# Control_Board.net
KiCad netlist of a schematic drawn in EAGLE
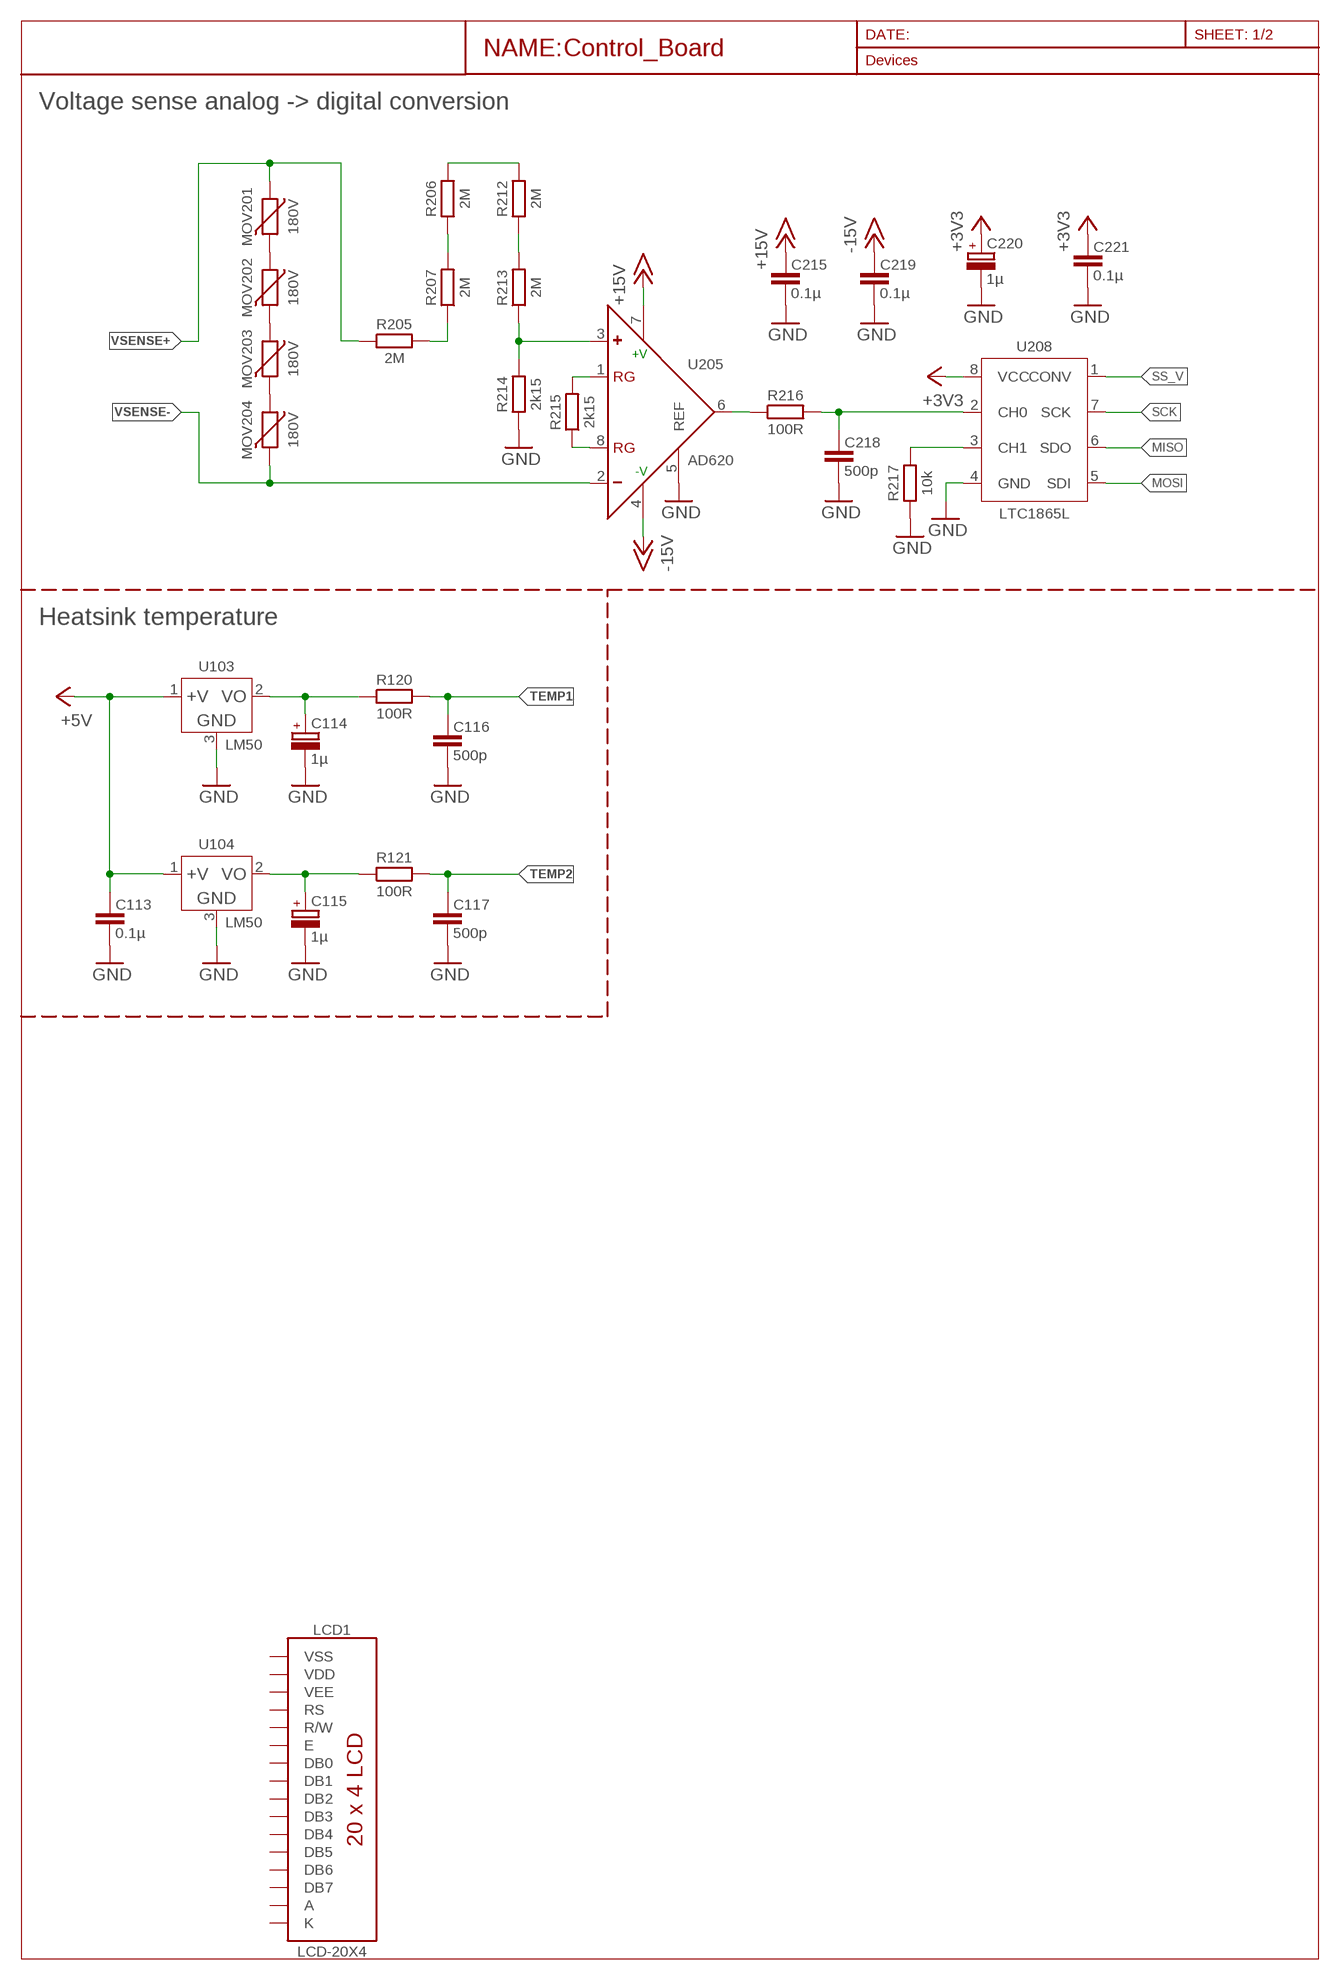
[diagram p0: schematic, sheet 1]
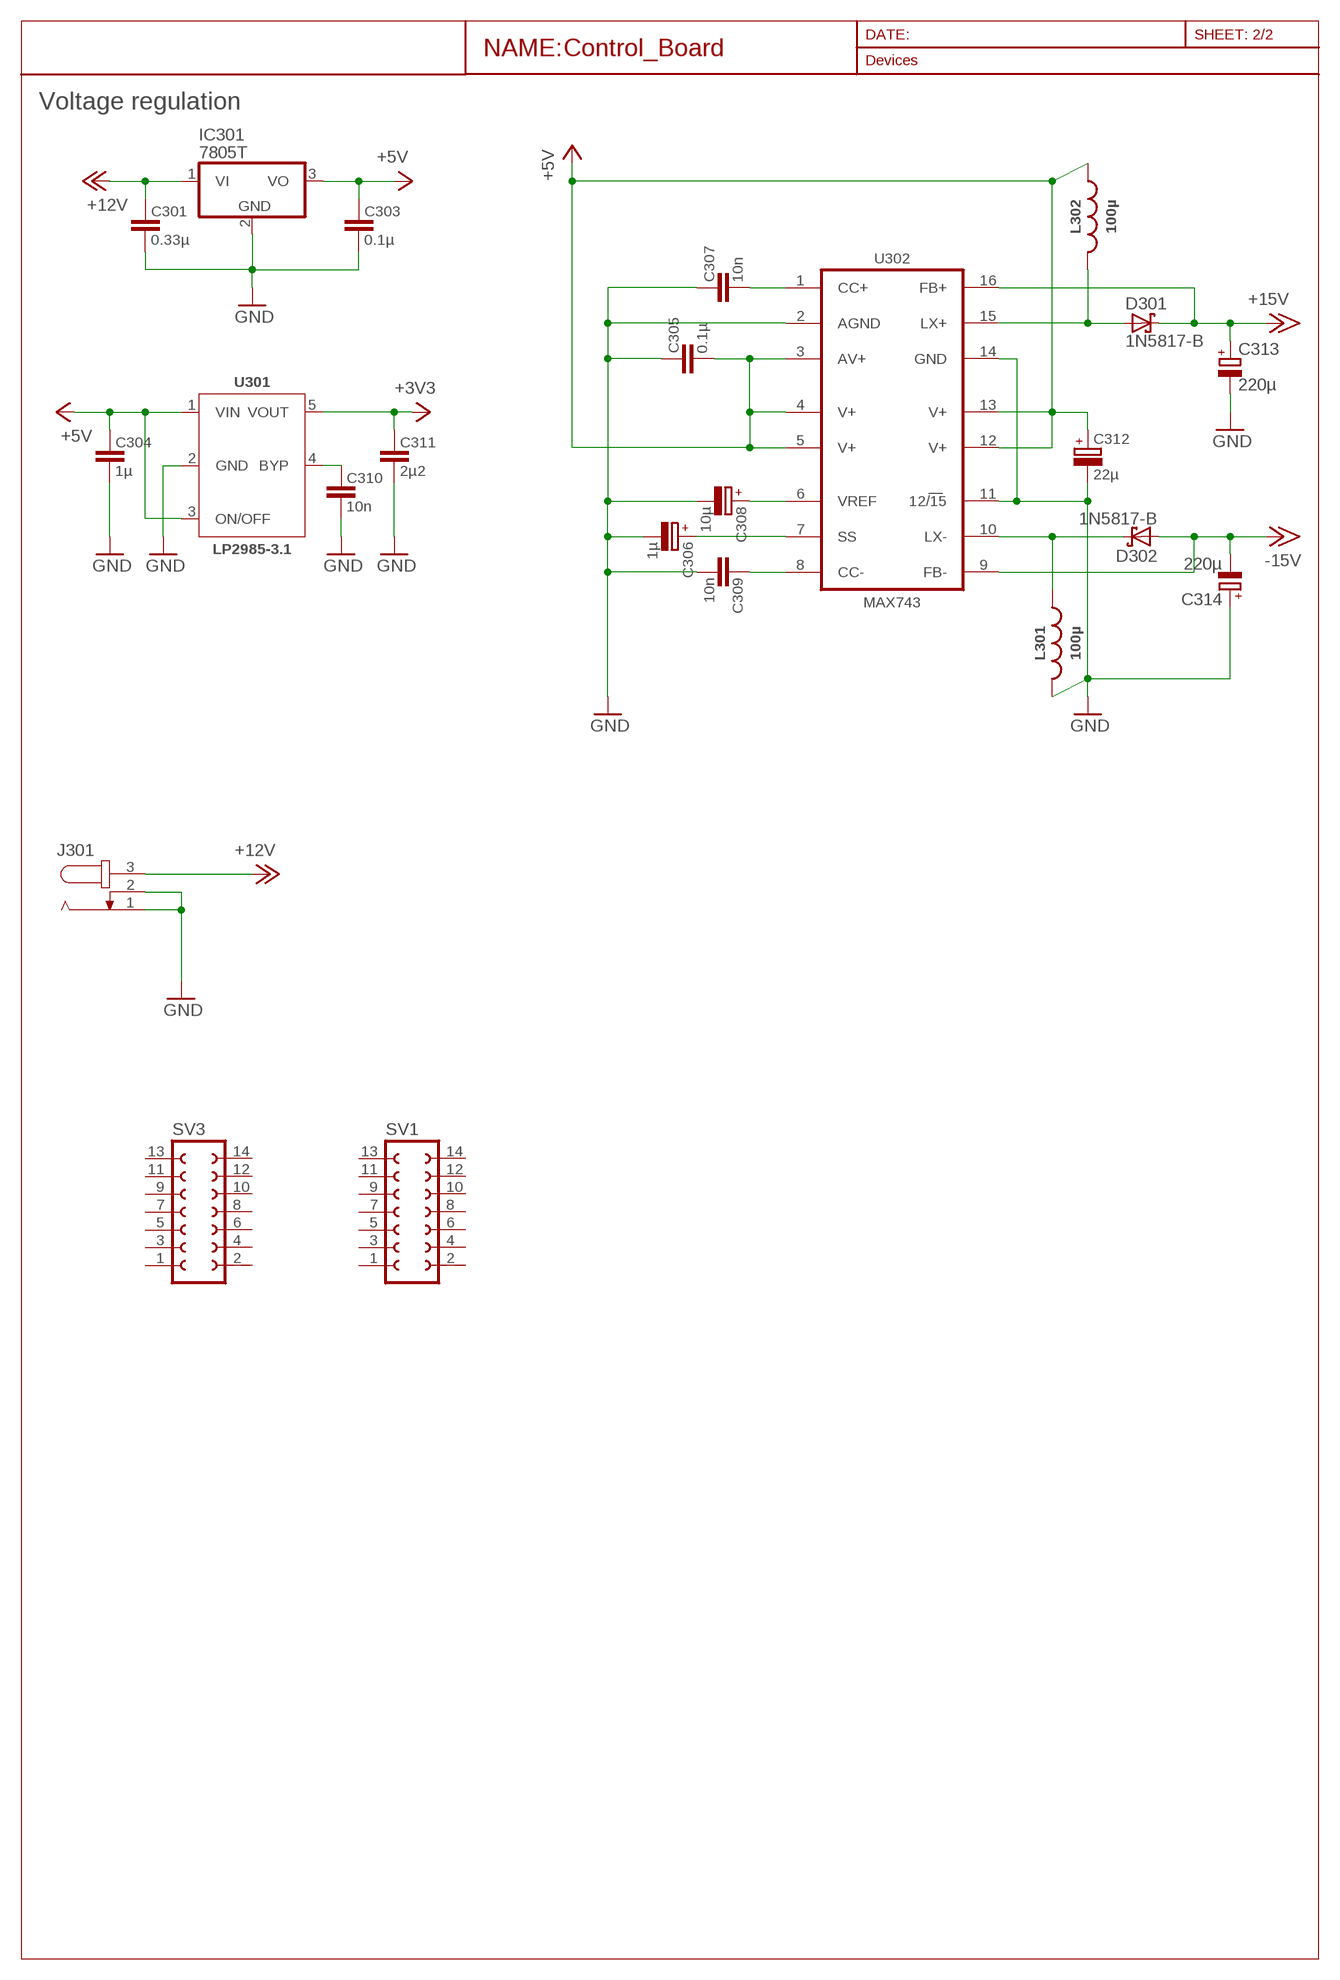
[diagram p1: schematic, sheet 2]

(export (version "E")
  (design (tool "Eeschema 10.0.6"))
  (components
    (comp (ref "C113")
      (value "0.1µ")
      (footprint "eagle-import:C3216")
      (libsource (lib "eagle-import") (part "C-EU-3216"))
    )
    (comp (ref "C114")
      (value "1µ")
      (footprint "eagle-import:CT3216")
      (libsource (lib "eagle-import") (part "CPOL-3216-A"))
    )
    (comp (ref "C115")
      (value "1µ")
      (footprint "eagle-import:CT3216")
      (libsource (lib "eagle-import") (part "CPOL-3216-A"))
    )
    (comp (ref "C116")
      (value "500p")
      (footprint "eagle-import:C1608")
      (libsource (lib "eagle-import") (part "C-EU-1608"))
    )
    (comp (ref "C117")
      (value "500p")
      (footprint "eagle-import:C1608")
      (libsource (lib "eagle-import") (part "C-EU-1608"))
    )
    (comp (ref "C215")
      (value "0.1µ")
      (footprint "eagle-import:C3216")
      (libsource (lib "eagle-import") (part "C-EU-3216"))
    )
    (comp (ref "C218")
      (value "500p")
      (footprint "eagle-import:C1608")
      (libsource (lib "eagle-import") (part "C-EU-1608"))
    )
    (comp (ref "C219")
      (value "0.1µ")
      (footprint "eagle-import:C3216")
      (libsource (lib "eagle-import") (part "C-EU-3216"))
    )
    (comp (ref "C220")
      (value "1µ")
      (footprint "eagle-import:CT3216")
      (libsource (lib "eagle-import") (part "CPOL-3216-A"))
    )
    (comp (ref "C221")
      (value "0.1µ")
      (footprint "eagle-import:C3216")
      (libsource (lib "eagle-import") (part "C-EU-3216"))
    )
    (comp (ref "LCD1")
      (value "LCD-20X4")
      (footprint "eagle-import:4X20_LED")
      (libsource (lib "eagle-import") (part "LCD-20X4"))
    )
    (comp (ref "MOV201")
      (value "180V")
      (footprint "eagle-import:R3225W")
      (libsource (lib "eagle-import") (part "MOV-3225"))
    )
    (comp (ref "MOV202")
      (value "180V")
      (footprint "eagle-import:R3225W")
      (libsource (lib "eagle-import") (part "MOV-3225"))
    )
    (comp (ref "MOV203")
      (value "180V")
      (footprint "eagle-import:R3225W")
      (libsource (lib "eagle-import") (part "MOV-3225"))
    )
    (comp (ref "MOV204")
      (value "180V")
      (footprint "eagle-import:R3225W")
      (libsource (lib "eagle-import") (part "MOV-3225"))
    )
    (comp (ref "R120")
      (value "100R")
      (footprint "eagle-import:R2012W")
      (libsource (lib "eagle-import") (part "R-EU-2012"))
    )
    (comp (ref "R121")
      (value "100R")
      (footprint "eagle-import:R2012W")
      (libsource (lib "eagle-import") (part "R-EU-2012"))
    )
    (comp (ref "R205")
      (value "2M")
      (footprint "eagle-import:R3216W")
      (libsource (lib "eagle-import") (part "R-EU-3216"))
    )
    (comp (ref "R206")
      (value "2M")
      (footprint "eagle-import:R3216W")
      (libsource (lib "eagle-import") (part "R-EU-3216"))
    )
    (comp (ref "R207")
      (value "2M")
      (footprint "eagle-import:R3216W")
      (libsource (lib "eagle-import") (part "R-EU-3216"))
    )
    (comp (ref "R212")
      (value "2M")
      (footprint "eagle-import:R3216W")
      (libsource (lib "eagle-import") (part "R-EU-3216"))
    )
    (comp (ref "R213")
      (value "2M")
      (footprint "eagle-import:R3216W")
      (libsource (lib "eagle-import") (part "R-EU-3216"))
    )
    (comp (ref "R214")
      (value "2k15")
      (footprint "eagle-import:R2012W")
      (libsource (lib "eagle-import") (part "R-EU-2012"))
    )
    (comp (ref "R215")
      (value "2k15")
      (footprint "eagle-import:R2012W")
      (libsource (lib "eagle-import") (part "R-EU-2012"))
    )
    (comp (ref "R216")
      (value "100R")
      (footprint "eagle-import:R2012W")
      (libsource (lib "eagle-import") (part "R-EU-2012"))
    )
    (comp (ref "R217")
      (value "10k")
      (footprint "eagle-import:R1608")
      (libsource (lib "eagle-import") (part "R-EU-1608"))
    )
    (comp (ref "U103")
      (value "LM50")
      (footprint "eagle-import:SOT23W")
      (libsource (lib "eagle-import") (part "LM50"))
    )
    (comp (ref "U104")
      (value "LM50")
      (footprint "eagle-import:SOT23W")
      (libsource (lib "eagle-import") (part "LM50"))
    )
    (comp (ref "U205")
      (value "AD620")
      (footprint "eagle-import:SO8")
      (libsource (lib "eagle-import") (part "AD620R-8"))
    )
    (comp (ref "U208")
      (value "LTC1865L")
      (footprint "eagle-import:SO8")
      (libsource (lib "eagle-import") (part "LTC1865L"))
    )
    (comp (ref "C301")
      (value "0.33µ")
      (footprint "eagle-import:C3216")
      (libsource (lib "eagle-import") (part "C-EU-3216"))
    )
    (comp (ref "C303")
      (value "0.1µ")
      (footprint "eagle-import:C3216")
      (libsource (lib "eagle-import") (part "C-EU-3216"))
    )
    (comp (ref "C304")
      (value "1µ")
      (footprint "eagle-import:C3216")
      (libsource (lib "eagle-import") (part "C-EU-3216"))
    )
    (comp (ref "C305")
      (value "0.1µ")
      (footprint "eagle-import:C3216")
      (libsource (lib "eagle-import") (part "C-EU-3216"))
    )
    (comp (ref "C306")
      (value "1µ")
      (footprint "eagle-import:CT3216")
      (libsource (lib "eagle-import") (part "CPOL-3216-A"))
    )
    (comp (ref "C307")
      (value "10n")
      (footprint "eagle-import:C3216")
      (libsource (lib "eagle-import") (part "C-EU-3216"))
    )
    (comp (ref "C308")
      (value "10µ")
      (footprint "eagle-import:CT6032")
      (libsource (lib "eagle-import") (part "CPOL-6032-C"))
    )
    (comp (ref "C309")
      (value "10n")
      (footprint "eagle-import:C3216")
      (libsource (lib "eagle-import") (part "C-EU-3216"))
    )
    (comp (ref "C310")
      (value "10n")
      (footprint "eagle-import:C3216")
      (libsource (lib "eagle-import") (part "C-EU-3216"))
    )
    (comp (ref "C311")
      (value "2µ2")
      (footprint "eagle-import:C3216")
      (libsource (lib "eagle-import") (part "C-EU-3216"))
    )
    (comp (ref "C312")
      (value "22µ")
      (footprint "eagle-import:CT6032")
      (libsource (lib "eagle-import") (part "CPOL-6032-C"))
    )
    (comp (ref "C313")
      (value "220µ")
      (footprint "eagle-import:E3,5-10")
      (libsource (lib "eagle-import") (part "CPOL-EUE3.5-10"))
    )
    (comp (ref "C314")
      (value "220µ")
      (footprint "eagle-import:E3,5-10")
      (libsource (lib "eagle-import") (part "CPOL-EUE3.5-10"))
    )
    (comp (ref "D301")
      (value "1N5817-B")
      (footprint "eagle-import:DO41-7.6")
      (libsource (lib "eagle-import") (part "1N5817-B"))
    )
    (comp (ref "D302")
      (value "1N5817-B")
      (footprint "eagle-import:DO41-7.6")
      (libsource (lib "eagle-import") (part "1N5817-B"))
    )
    (comp (ref "IC301")
      (value "7805T")
      (footprint "eagle-import:TO220H")
      (libsource (lib "eagle-import") (part "78T05"))
    )
    (comp (ref "J301")
      (value "JACK-PLUG0")
      (footprint "eagle-import:SPC4077")
      (libsource (lib "eagle-import") (part "JACK-PLUG0"))
    )
    (comp (ref "L301")
      (value "100µ")
      (footprint "eagle-import:SRN1060")
      (libsource (lib "eagle-import") (part "L-EUSRN1060"))
    )
    (comp (ref "L302")
      (value "100µ")
      (footprint "eagle-import:SRN1060")
      (libsource (lib "eagle-import") (part "L-EUSRN1060"))
    )
    (comp (ref "SV1")
      (value "FE07-2W")
      (footprint "eagle-import:FE07-2W")
      (libsource (lib "eagle-import") (part "FE07-2W"))
    )
    (comp (ref "SV3")
      (value "FE07-2W")
      (footprint "eagle-import:FE07-2W")
      (libsource (lib "eagle-import") (part "FE07-2W"))
    )
    (comp (ref "U301")
      (value "LP2985-3.1")
      (footprint "eagle-import:SOT23-5L")
      (libsource (lib "eagle-import") (part "LP2985-3.1"))
    )
    (comp (ref "U302")
      (value "MAX743")
      (footprint "eagle-import:SO16W")
      (libsource (lib "eagle-import") (part "MAX743WE"))
    )
  )
  (nets
    (net (code "1") (name "+3V3") (class "Default")
      (node (ref "C220") (pin "+") (pinfunction "+_+") (pintype "passive"))
      (node (ref "C221") (pin "1") (pinfunction "1_1") (pintype "passive"))
      (node (ref "C311") (pin "1") (pinfunction "1_1") (pintype "passive"))
      (node (ref "U208") (pin "8") (pinfunction "VCC_8") (pintype "power_in"))
      (node (ref "U301") (pin "5") (pinfunction "VOUT_5") (pintype "power_in"))
    )
    (net (code "2") (name "+5V") (class "Default")
      (node (ref "C113") (pin "1") (pinfunction "1_1") (pintype "passive"))
      (node (ref "C303") (pin "1") (pinfunction "1_1") (pintype "passive"))
      (node (ref "C304") (pin "1") (pinfunction "1_1") (pintype "passive"))
      (node (ref "C305") (pin "2") (pinfunction "2_2") (pintype "passive"))
      (node (ref "C312") (pin "+") (pinfunction "+_+") (pintype "passive"))
      (node (ref "IC301") (pin "3") (pinfunction "VO_3") (pintype "passive"))
      (node (ref "L302") (pin "1") (pinfunction "1_1") (pintype "passive"))
      (node (ref "U103") (pin "1") (pinfunction "+V_1") (pintype "power_in"))
      (node (ref "U104") (pin "1") (pinfunction "+V_1") (pintype "power_in"))
      (node (ref "U301") (pin "1") (pinfunction "VIN_1") (pintype "power_in"))
      (node (ref "U301") (pin "3") (pinfunction "ON/OFF_3") (pintype "input"))
      (node (ref "U302") (pin "12") (pinfunction "V+_12") (pintype "input"))
      (node (ref "U302") (pin "13") (pinfunction "V+_13") (pintype "input"))
      (node (ref "U302") (pin "3") (pinfunction "AV+_3") (pintype "input"))
      (node (ref "U302") (pin "4") (pinfunction "V+_4") (pintype "input"))
      (node (ref "U302") (pin "5") (pinfunction "V+_5") (pintype "input"))
    )
    (net (code "3") (name "+12V") (class "Default")
      (node (ref "C301") (pin "1") (pinfunction "1_1") (pintype "passive"))
      (node (ref "IC301") (pin "1") (pinfunction "VI_1") (pintype "input"))
      (node (ref "J301") (pin "3") (pinfunction "3_3") (pintype "passive"))
    )
    (net (code "4") (name "+15V") (class "Default")
      (node (ref "C215") (pin "1") (pinfunction "1_1") (pintype "passive"))
      (node (ref "C313") (pin "+") (pinfunction "+_+") (pintype "passive"))
      (node (ref "D301") (pin "C") (pinfunction "C_C") (pintype "passive"))
      (node (ref "U205") (pin "7") (pinfunction "+V_7") (pintype "power_in"))
      (node (ref "U302") (pin "16") (pinfunction "FB+_16") (pintype "input"))
    )
    (net (code "5") (name "-15V") (class "Default")
      (node (ref "C219") (pin "1") (pinfunction "1_1") (pintype "passive"))
      (node (ref "C314") (pin "-") (pinfunction "-_-") (pintype "passive"))
      (node (ref "D302") (pin "A") (pinfunction "A_A") (pintype "passive"))
      (node (ref "U205") (pin "4") (pinfunction "-V_4") (pintype "power_in"))
      (node (ref "U302") (pin "9") (pinfunction "FB-_9") (pintype "input"))
    )
    (net (code "6") (name "A") (class "Default")
      (node (ref "LCD1") (pin "15") (pinfunction "A_15") (pintype "power_in"))
    )
    (net (code "7") (name "GND") (class "Default")
      (node (ref "C113") (pin "2") (pinfunction "2_2") (pintype "passive"))
      (node (ref "C114") (pin "-") (pinfunction "-_-") (pintype "passive"))
      (node (ref "C115") (pin "-") (pinfunction "-_-") (pintype "passive"))
      (node (ref "C116") (pin "2") (pinfunction "2_2") (pintype "passive"))
      (node (ref "C117") (pin "2") (pinfunction "2_2") (pintype "passive"))
      (node (ref "C215") (pin "2") (pinfunction "2_2") (pintype "passive"))
      (node (ref "C218") (pin "2") (pinfunction "2_2") (pintype "passive"))
      (node (ref "C219") (pin "2") (pinfunction "2_2") (pintype "passive"))
      (node (ref "C220") (pin "-") (pinfunction "-_-") (pintype "passive"))
      (node (ref "C221") (pin "2") (pinfunction "2_2") (pintype "passive"))
      (node (ref "C301") (pin "2") (pinfunction "2_2") (pintype "passive"))
      (node (ref "C303") (pin "2") (pinfunction "2_2") (pintype "passive"))
      (node (ref "C304") (pin "2") (pinfunction "2_2") (pintype "passive"))
      (node (ref "C305") (pin "1") (pinfunction "1_1") (pintype "passive"))
      (node (ref "C306") (pin "-") (pinfunction "-_-") (pintype "passive"))
      (node (ref "C307") (pin "1") (pinfunction "1_1") (pintype "passive"))
      (node (ref "C308") (pin "-") (pinfunction "-_-") (pintype "passive"))
      (node (ref "C309") (pin "2") (pinfunction "2_2") (pintype "passive"))
      (node (ref "C310") (pin "2") (pinfunction "2_2") (pintype "passive"))
      (node (ref "C311") (pin "2") (pinfunction "2_2") (pintype "passive"))
      (node (ref "C312") (pin "-") (pinfunction "-_-") (pintype "passive"))
      (node (ref "C313") (pin "-") (pinfunction "-_-") (pintype "passive"))
      (node (ref "C314") (pin "+") (pinfunction "+_+") (pintype "passive"))
      (node (ref "IC301") (pin "2") (pinfunction "GND_2") (pintype "passive"))
      (node (ref "J301") (pin "1") (pinfunction "1_1") (pintype "passive"))
      (node (ref "J301") (pin "2") (pinfunction "2_2") (pintype "passive"))
      (node (ref "L301") (pin "2") (pinfunction "2_2") (pintype "passive"))
      (node (ref "R214") (pin "1") (pinfunction "1_1") (pintype "passive"))
      (node (ref "R217") (pin "1") (pinfunction "1_1") (pintype "passive"))
      (node (ref "U103") (pin "3") (pinfunction "GND_3") (pintype "power_in"))
      (node (ref "U104") (pin "3") (pinfunction "GND_3") (pintype "power_in"))
      (node (ref "U205") (pin "5") (pinfunction "REF_5") (pintype "passive"))
      (node (ref "U208") (pin "4") (pinfunction "GND_4") (pintype "bidirectional"))
      (node (ref "U301") (pin "2") (pinfunction "GND_2") (pintype "power_in"))
      (node (ref "U302") (pin "11") (pinfunction "12/15_11") (pintype "input"))
      (node (ref "U302") (pin "14") (pinfunction "GND_14") (pintype "power_in"))
      (node (ref "U302") (pin "2") (pinfunction "AGND_2") (pintype "power_in"))
    )
    (net (code "8") (name "K") (class "Default")
      (node (ref "LCD1") (pin "16") (pinfunction "K_16") (pintype "power_in"))
    )
    (net (code "9") (name "MISO") (class "Default")
      (node (ref "U208") (pin "6") (pinfunction "SDO_6") (pintype "output"))
    )
    (net (code "10") (name "MOSI") (class "Default")
      (node (ref "U208") (pin "5") (pinfunction "SDI_5") (pintype "input"))
    )
    (net (code "11") (name "Net-(MOV201-Pad2)") (class "Default")
      (node (ref "MOV201") (pin "2") (pinfunction "2_2") (pintype "passive"))
      (node (ref "MOV202") (pin "1") (pinfunction "1_1") (pintype "passive"))
    )
    (net (code "12") (name "Net-(MOV202-Pad2)") (class "Default")
      (node (ref "MOV202") (pin "2") (pinfunction "2_2") (pintype "passive"))
      (node (ref "MOV203") (pin "1") (pinfunction "1_1") (pintype "passive"))
    )
    (net (code "13") (name "Net-(MOV203-Pad2)") (class "Default")
      (node (ref "MOV203") (pin "2") (pinfunction "2_2") (pintype "passive"))
      (node (ref "MOV204") (pin "1") (pinfunction "1_1") (pintype "passive"))
    )
    (net (code "14") (name "Net-(R205-Pad2)") (class "Default")
      (node (ref "R205") (pin "2") (pinfunction "2_2") (pintype "passive"))
      (node (ref "R207") (pin "1") (pinfunction "1_1") (pintype "passive"))
    )
    (net (code "15") (name "Net-(R206-Pad1)") (class "Default")
      (node (ref "R206") (pin "1") (pinfunction "1_1") (pintype "passive"))
      (node (ref "R207") (pin "2") (pinfunction "2_2") (pintype "passive"))
    )
    (net (code "16") (name "Net-(R206-Pad2)") (class "Default")
      (node (ref "R206") (pin "2") (pinfunction "2_2") (pintype "passive"))
      (node (ref "R212") (pin "2") (pinfunction "2_2") (pintype "passive"))
    )
    (net (code "17") (name "Net-(R212-Pad1)") (class "Default")
      (node (ref "R212") (pin "1") (pinfunction "1_1") (pintype "passive"))
      (node (ref "R213") (pin "2") (pinfunction "2_2") (pintype "passive"))
    )
    (net (code "18") (name "Net-(R215-Pad1)") (class "Default")
      (node (ref "R215") (pin "1") (pinfunction "1_1") (pintype "passive"))
      (node (ref "U205") (pin "8") (pinfunction "RG_8") (pintype "passive"))
    )
    (net (code "19") (name "Net-(R215-Pad2)") (class "Default")
      (node (ref "R215") (pin "2") (pinfunction "2_2") (pintype "passive"))
      (node (ref "U205") (pin "1") (pinfunction "RG_1") (pintype "passive"))
    )
    (net (code "20") (name "Net-(U103-VO)") (class "Default")
      (node (ref "C114") (pin "+") (pinfunction "+_+") (pintype "passive"))
      (node (ref "R120") (pin "1") (pinfunction "1_1") (pintype "passive"))
      (node (ref "U103") (pin "2") (pinfunction "VO_2") (pintype "output"))
    )
    (net (code "21") (name "Net-(U104-VO)") (class "Default")
      (node (ref "C115") (pin "+") (pinfunction "+_+") (pintype "passive"))
      (node (ref "R121") (pin "1") (pinfunction "1_1") (pintype "passive"))
      (node (ref "U104") (pin "2") (pinfunction "VO_2") (pintype "output"))
    )
    (net (code "22") (name "Net-(U205-+)") (class "Default")
      (node (ref "R213") (pin "1") (pinfunction "1_1") (pintype "passive"))
      (node (ref "R214") (pin "2") (pinfunction "2_2") (pintype "passive"))
      (node (ref "U205") (pin "3") (pinfunction "+_3") (pintype "input"))
    )
    (net (code "23") (name "Net-(U205-OUT)") (class "Default")
      (node (ref "R216") (pin "1") (pinfunction "1_1") (pintype "passive"))
      (node (ref "U205") (pin "6") (pinfunction "OUT_6") (pintype "output"))
    )
    (net (code "24") (name "Net-(U208-CH0)") (class "Default")
      (node (ref "C218") (pin "1") (pinfunction "1_1") (pintype "passive"))
      (node (ref "R216") (pin "2") (pinfunction "2_2") (pintype "passive"))
      (node (ref "U208") (pin "2") (pinfunction "CH0_2") (pintype "input"))
    )
    (net (code "25") (name "Net-(U208-CH1)") (class "Default")
      (node (ref "R217") (pin "2") (pinfunction "2_2") (pintype "passive"))
      (node (ref "U208") (pin "3") (pinfunction "CH1_3") (pintype "input"))
    )
    (net (code "26") (name "Net-(U301-BYP)") (class "Default")
      (node (ref "C310") (pin "1") (pinfunction "1_1") (pintype "passive"))
      (node (ref "U301") (pin "4") (pinfunction "BYP_4") (pintype "power_in"))
    )
    (net (code "27") (name "Net-(U302-CC+)") (class "Default")
      (node (ref "C307") (pin "2") (pinfunction "2_2") (pintype "passive"))
      (node (ref "U302") (pin "1") (pinfunction "CC+_1") (pintype "passive"))
    )
    (net (code "28") (name "Net-(U302-CC-)") (class "Default")
      (node (ref "C309") (pin "1") (pinfunction "1_1") (pintype "passive"))
      (node (ref "U302") (pin "8") (pinfunction "CC-_8") (pintype "passive"))
    )
    (net (code "29") (name "Net-(U302-LX+)") (class "Default")
      (node (ref "D301") (pin "A") (pinfunction "A_A") (pintype "passive"))
      (node (ref "L302") (pin "2") (pinfunction "2_2") (pintype "passive"))
      (node (ref "U302") (pin "15") (pinfunction "LX+_15") (pintype "passive"))
    )
    (net (code "30") (name "Net-(U302-LX-)") (class "Default")
      (node (ref "D302") (pin "C") (pinfunction "C_C") (pintype "passive"))
      (node (ref "L301") (pin "1") (pinfunction "1_1") (pintype "passive"))
      (node (ref "U302") (pin "10") (pinfunction "LX-_10") (pintype "passive"))
    )
    (net (code "31") (name "Net-(U302-SS)") (class "Default")
      (node (ref "C306") (pin "+") (pinfunction "+_+") (pintype "passive"))
      (node (ref "U302") (pin "7") (pinfunction "SS_7") (pintype "passive"))
    )
    (net (code "32") (name "Net-(U302-VREF)") (class "Default")
      (node (ref "C308") (pin "+") (pinfunction "+_+") (pintype "passive"))
      (node (ref "U302") (pin "6") (pinfunction "VREF_6") (pintype "power_in"))
    )
    (net (code "33") (name "SCK") (class "Default")
      (node (ref "U208") (pin "7") (pinfunction "SCK_7") (pintype "input"))
    )
    (net (code "34") (name "SS_V") (class "Default")
      (node (ref "U208") (pin "1") (pinfunction "CONV_1") (pintype "input"))
    )
    (net (code "35") (name "TEMP1") (class "Default")
      (node (ref "C116") (pin "1") (pinfunction "1_1") (pintype "passive"))
      (node (ref "R120") (pin "2") (pinfunction "2_2") (pintype "passive"))
    )
    (net (code "36") (name "TEMP2") (class "Default")
      (node (ref "C117") (pin "1") (pinfunction "1_1") (pintype "passive"))
      (node (ref "R121") (pin "2") (pinfunction "2_2") (pintype "passive"))
    )
    (net (code "37") (name "VDD") (class "Default")
      (node (ref "LCD1") (pin "2") (pinfunction "VDD_2") (pintype "power_in"))
    )
    (net (code "38") (name "VEE") (class "Default")
      (node (ref "LCD1") (pin "3") (pinfunction "VEE_3") (pintype "power_in"))
    )
    (net (code "39") (name "VSENSE+") (class "Default")
      (node (ref "MOV201") (pin "1") (pinfunction "1_1") (pintype "passive"))
      (node (ref "R205") (pin "1") (pinfunction "1_1") (pintype "passive"))
    )
    (net (code "40") (name "VSENSE-") (class "Default")
      (node (ref "MOV204") (pin "2") (pinfunction "2_2") (pintype "passive"))
      (node (ref "U205") (pin "2") (pinfunction "-_2") (pintype "input"))
    )
    (net (code "41") (name "VSS") (class "Default")
      (node (ref "LCD1") (pin "1") (pinfunction "VSS_1") (pintype "power_in"))
    )
    (net (code "42") (name "unconnected-(LCD1-DB0-Pad7)") (class "Default")
      (node (ref "LCD1") (pin "7") (pinfunction "DB0_7") (pintype "bidirectional"))
    )
    (net (code "43") (name "unconnected-(LCD1-DB1-Pad8)") (class "Default")
      (node (ref "LCD1") (pin "8") (pinfunction "DB1_8") (pintype "bidirectional"))
    )
    (net (code "44") (name "unconnected-(LCD1-DB2-Pad9)") (class "Default")
      (node (ref "LCD1") (pin "9") (pinfunction "DB2_9") (pintype "bidirectional"))
    )
    (net (code "45") (name "unconnected-(LCD1-DB3-Pad10)") (class "Default")
      (node (ref "LCD1") (pin "10") (pinfunction "DB3_10") (pintype "bidirectional"))
    )
    (net (code "46") (name "unconnected-(LCD1-DB4-Pad11)") (class "Default")
      (node (ref "LCD1") (pin "11") (pinfunction "DB4_11") (pintype "bidirectional"))
    )
    (net (code "47") (name "unconnected-(LCD1-DB5-Pad12)") (class "Default")
      (node (ref "LCD1") (pin "12") (pinfunction "DB5_12") (pintype "bidirectional"))
    )
    (net (code "48") (name "unconnected-(LCD1-DB6-Pad13)") (class "Default")
      (node (ref "LCD1") (pin "13") (pinfunction "DB6_13") (pintype "bidirectional"))
    )
    (net (code "49") (name "unconnected-(LCD1-DB7-Pad14)") (class "Default")
      (node (ref "LCD1") (pin "14") (pinfunction "DB7_14") (pintype "bidirectional"))
    )
    (net (code "50") (name "unconnected-(LCD1-E-Pad6)") (class "Default")
      (node (ref "LCD1") (pin "6") (pinfunction "E_6") (pintype "input"))
    )
    (net (code "51") (name "unconnected-(LCD1-RS-Pad4)") (class "Default")
      (node (ref "LCD1") (pin "4") (pinfunction "RS_4") (pintype "input"))
    )
    (net (code "52") (name "unconnected-(LCD1-R{slash}W-Pad5)") (class "Default")
      (node (ref "LCD1") (pin "5") (pinfunction "R/W_5") (pintype "input"))
    )
    (net (code "53") (name "unconnected-(SV1-Pad1)") (class "Default")
      (node (ref "SV1") (pin "1") (pinfunction "1_1") (pintype "passive"))
    )
    (net (code "54") (name "unconnected-(SV1-Pad2)") (class "Default")
      (node (ref "SV1") (pin "2") (pinfunction "2_2") (pintype "passive"))
    )
    (net (code "55") (name "unconnected-(SV1-Pad3)") (class "Default")
      (node (ref "SV1") (pin "3") (pinfunction "3_3") (pintype "passive"))
    )
    (net (code "56") (name "unconnected-(SV1-Pad4)") (class "Default")
      (node (ref "SV1") (pin "4") (pinfunction "4_4") (pintype "passive"))
    )
    (net (code "57") (name "unconnected-(SV1-Pad5)") (class "Default")
      (node (ref "SV1") (pin "5") (pinfunction "5_5") (pintype "passive"))
    )
    (net (code "58") (name "unconnected-(SV1-Pad6)") (class "Default")
      (node (ref "SV1") (pin "6") (pinfunction "6_6") (pintype "passive"))
    )
    (net (code "59") (name "unconnected-(SV1-Pad7)") (class "Default")
      (node (ref "SV1") (pin "7") (pinfunction "7_7") (pintype "passive"))
    )
    (net (code "60") (name "unconnected-(SV1-Pad8)") (class "Default")
      (node (ref "SV1") (pin "8") (pinfunction "8_8") (pintype "passive"))
    )
    (net (code "61") (name "unconnected-(SV1-Pad9)") (class "Default")
      (node (ref "SV1") (pin "9") (pinfunction "9_9") (pintype "passive"))
    )
    (net (code "62") (name "unconnected-(SV1-Pad10)") (class "Default")
      (node (ref "SV1") (pin "10") (pinfunction "10_10") (pintype "passive"))
    )
    (net (code "63") (name "unconnected-(SV1-Pad11)") (class "Default")
      (node (ref "SV1") (pin "11") (pinfunction "11_11") (pintype "passive"))
    )
    (net (code "64") (name "unconnected-(SV1-Pad12)") (class "Default")
      (node (ref "SV1") (pin "12") (pinfunction "12_12") (pintype "passive"))
    )
    (net (code "65") (name "unconnected-(SV1-Pad13)") (class "Default")
      (node (ref "SV1") (pin "13") (pinfunction "13_13") (pintype "passive"))
    )
    (net (code "66") (name "unconnected-(SV1-Pad14)") (class "Default")
      (node (ref "SV1") (pin "14") (pinfunction "14_14") (pintype "passive"))
    )
    (net (code "67") (name "unconnected-(SV3-Pad1)") (class "Default")
      (node (ref "SV3") (pin "1") (pinfunction "1_1") (pintype "passive"))
    )
    (net (code "68") (name "unconnected-(SV3-Pad2)") (class "Default")
      (node (ref "SV3") (pin "2") (pinfunction "2_2") (pintype "passive"))
    )
    (net (code "69") (name "unconnected-(SV3-Pad3)") (class "Default")
      (node (ref "SV3") (pin "3") (pinfunction "3_3") (pintype "passive"))
    )
    (net (code "70") (name "unconnected-(SV3-Pad4)") (class "Default")
      (node (ref "SV3") (pin "4") (pinfunction "4_4") (pintype "passive"))
    )
    (net (code "71") (name "unconnected-(SV3-Pad5)") (class "Default")
      (node (ref "SV3") (pin "5") (pinfunction "5_5") (pintype "passive"))
    )
    (net (code "72") (name "unconnected-(SV3-Pad6)") (class "Default")
      (node (ref "SV3") (pin "6") (pinfunction "6_6") (pintype "passive"))
    )
    (net (code "73") (name "unconnected-(SV3-Pad7)") (class "Default")
      (node (ref "SV3") (pin "7") (pinfunction "7_7") (pintype "passive"))
    )
    (net (code "74") (name "unconnected-(SV3-Pad8)") (class "Default")
      (node (ref "SV3") (pin "8") (pinfunction "8_8") (pintype "passive"))
    )
    (net (code "75") (name "unconnected-(SV3-Pad9)") (class "Default")
      (node (ref "SV3") (pin "9") (pinfunction "9_9") (pintype "passive"))
    )
    (net (code "76") (name "unconnected-(SV3-Pad10)") (class "Default")
      (node (ref "SV3") (pin "10") (pinfunction "10_10") (pintype "passive"))
    )
    (net (code "77") (name "unconnected-(SV3-Pad11)") (class "Default")
      (node (ref "SV3") (pin "11") (pinfunction "11_11") (pintype "passive"))
    )
    (net (code "78") (name "unconnected-(SV3-Pad12)") (class "Default")
      (node (ref "SV3") (pin "12") (pinfunction "12_12") (pintype "passive"))
    )
    (net (code "79") (name "unconnected-(SV3-Pad13)") (class "Default")
      (node (ref "SV3") (pin "13") (pinfunction "13_13") (pintype "passive"))
    )
    (net (code "80") (name "unconnected-(SV3-Pad14)") (class "Default")
      (node (ref "SV3") (pin "14") (pinfunction "14_14") (pintype "passive"))
    )
  )
)
